# additional-hardware.net
KiCad netlist of a schematic drawn in EAGLE
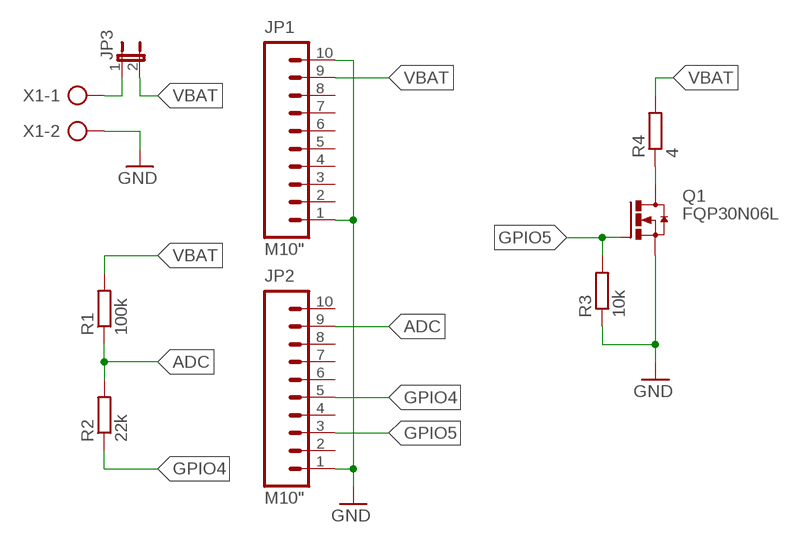
[diagram p0: schematic, sheet 1]

(export (version "E")
  (design (tool "Eeschema 10.0.6"))
  (components
    (comp (ref "JP1")
      (value "M10\"")
      (footprint "eagle-import:1X10")
      (libsource (lib "eagle-import") (part "M10{dblquote}"))
    )
    (comp (ref "JP2")
      (value "M10\"")
      (footprint "eagle-import:1X10")
      (libsource (lib "eagle-import") (part "M10{dblquote}"))
    )
    (comp (ref "JP3")
      (value "JP1E")
      (footprint "eagle-import:JP1")
      (libsource (lib "eagle-import") (part "JP1E"))
    )
    (comp (ref "Q1")
      (value "FQP30N06L")
      (footprint "eagle-import:TO-247AD-V")
      (libsource (lib "eagle-import") (part "IRFP251"))
    )
    (comp (ref "R1")
      (value "100k")
      (footprint "eagle-import:0309_12")
      (libsource (lib "eagle-import") (part "R-EU_0309/12"))
    )
    (comp (ref "R2")
      (value "22k")
      (footprint "eagle-import:0309_12")
      (libsource (lib "eagle-import") (part "R-EU_0309/12"))
    )
    (comp (ref "R3")
      (value "10k")
      (footprint "eagle-import:0309_12")
      (libsource (lib "eagle-import") (part "R-EU_0309/12"))
    )
    (comp (ref "R4")
      (value "4")
      (footprint "eagle-import:0309_12")
      (libsource (lib "eagle-import") (part "R-EU_0309/12"))
    )
    (comp (ref "X1")
      (value "AK500/2-H")
      (footprint "eagle-import:AK500_2-H")
      (libsource (lib "eagle-import") (part "AK500/2-H"))
    )
  )
  (nets
    (net (code "1") (name "ADC") (class "Default")
      (node (ref "JP2") (pin "9") (pinfunction "9_9") (pintype "passive"))
    )
    (net (code "2") (name "GND") (class "Default")
      (node (ref "JP1") (pin "1") (pinfunction "1_1") (pintype "passive"))
      (node (ref "JP1") (pin "10") (pinfunction "10_10") (pintype "passive"))
      (node (ref "JP2") (pin "1") (pinfunction "1_1") (pintype "passive"))
      (node (ref "Q1") (pin "S") (pinfunction "S_S") (pintype "passive"))
      (node (ref "R3") (pin "1") (pinfunction "1_1") (pintype "passive"))
      (node (ref "X1") (pin "2") (pinfunction "KL_2") (pintype "passive"))
    )
    (net (code "3") (name "GPIO4") (class "Default")
      (node (ref "JP2") (pin "5") (pinfunction "5_5") (pintype "passive"))
    )
    (net (code "4") (name "GPIO5") (class "Default")
      (node (ref "JP2") (pin "3") (pinfunction "3_3") (pintype "passive"))
    )
    (net (code "5") (name "Net-(Q1-PadD)") (class "Default")
      (node (ref "Q1") (pin "D") (pinfunction "D_D") (pintype "passive"))
      (node (ref "R4") (pin "1") (pinfunction "1_1") (pintype "passive"))
    )
    (net (code "6") (name "Net-(Q1-PadG)") (class "Default")
      (node (ref "Q1") (pin "G") (pinfunction "G_G") (pintype "passive"))
      (node (ref "R3") (pin "2") (pinfunction "2_2") (pintype "passive"))
    )
    (net (code "7") (name "Net-(R1-Pad1)") (class "Default")
      (node (ref "R1") (pin "1") (pinfunction "1_1") (pintype "passive"))
      (node (ref "R2") (pin "2") (pinfunction "2_2") (pintype "passive"))
    )
    (net (code "8") (name "Net-(X1A-KL)") (class "Default")
      (node (ref "JP3") (pin "1") (pinfunction "1_1") (pintype "passive"))
      (node (ref "X1") (pin "1") (pinfunction "KL_1") (pintype "passive"))
    )
    (net (code "9") (name "VBAT") (class "Default")
      (node (ref "JP1") (pin "9") (pinfunction "9_9") (pintype "passive"))
    )
    (net (code "10") (name "unconnected-(JP1-Pad2)") (class "Default")
      (node (ref "JP1") (pin "2") (pinfunction "2_2") (pintype "passive"))
    )
    (net (code "11") (name "unconnected-(JP1-Pad3)") (class "Default")
      (node (ref "JP1") (pin "3") (pinfunction "3_3") (pintype "passive"))
    )
    (net (code "12") (name "unconnected-(JP1-Pad4)") (class "Default")
      (node (ref "JP1") (pin "4") (pinfunction "4_4") (pintype "passive"))
    )
    (net (code "13") (name "unconnected-(JP1-Pad5)") (class "Default")
      (node (ref "JP1") (pin "5") (pinfunction "5_5") (pintype "passive"))
    )
    (net (code "14") (name "unconnected-(JP1-Pad6)") (class "Default")
      (node (ref "JP1") (pin "6") (pinfunction "6_6") (pintype "passive"))
    )
    (net (code "15") (name "unconnected-(JP1-Pad7)") (class "Default")
      (node (ref "JP1") (pin "7") (pinfunction "7_7") (pintype "passive"))
    )
    (net (code "16") (name "unconnected-(JP1-Pad8)") (class "Default")
      (node (ref "JP1") (pin "8") (pinfunction "8_8") (pintype "passive"))
    )
    (net (code "17") (name "unconnected-(JP2-Pad2)") (class "Default")
      (node (ref "JP2") (pin "2") (pinfunction "2_2") (pintype "passive"))
    )
    (net (code "18") (name "unconnected-(JP2-Pad4)") (class "Default")
      (node (ref "JP2") (pin "4") (pinfunction "4_4") (pintype "passive"))
    )
    (net (code "19") (name "unconnected-(JP2-Pad6)") (class "Default")
      (node (ref "JP2") (pin "6") (pinfunction "6_6") (pintype "passive"))
    )
    (net (code "20") (name "unconnected-(JP2-Pad7)") (class "Default")
      (node (ref "JP2") (pin "7") (pinfunction "7_7") (pintype "passive"))
    )
    (net (code "21") (name "unconnected-(JP2-Pad8)") (class "Default")
      (node (ref "JP2") (pin "8") (pinfunction "8_8") (pintype "passive"))
    )
    (net (code "22") (name "unconnected-(JP2-Pad10)") (class "Default")
      (node (ref "JP2") (pin "10") (pinfunction "10_10") (pintype "passive"))
    )
    (net (code "23") (name "unconnected-(JP3-Pad2)") (class "Default")
      (node (ref "JP3") (pin "2") (pinfunction "2_2") (pintype "passive"))
    )
    (net (code "24") (name "unconnected-(R1-Pad2)") (class "Default")
      (node (ref "R1") (pin "2") (pinfunction "2_2") (pintype "passive"))
    )
    (net (code "25") (name "unconnected-(R2-Pad1)") (class "Default")
      (node (ref "R2") (pin "1") (pinfunction "1_1") (pintype "passive"))
    )
    (net (code "26") (name "unconnected-(R4-Pad2)") (class "Default")
      (node (ref "R4") (pin "2") (pinfunction "2_2") (pintype "passive"))
    )
  )
)
